# Motor_Driver.net
KiCad netlist of a schematic drawn in Altium Designer
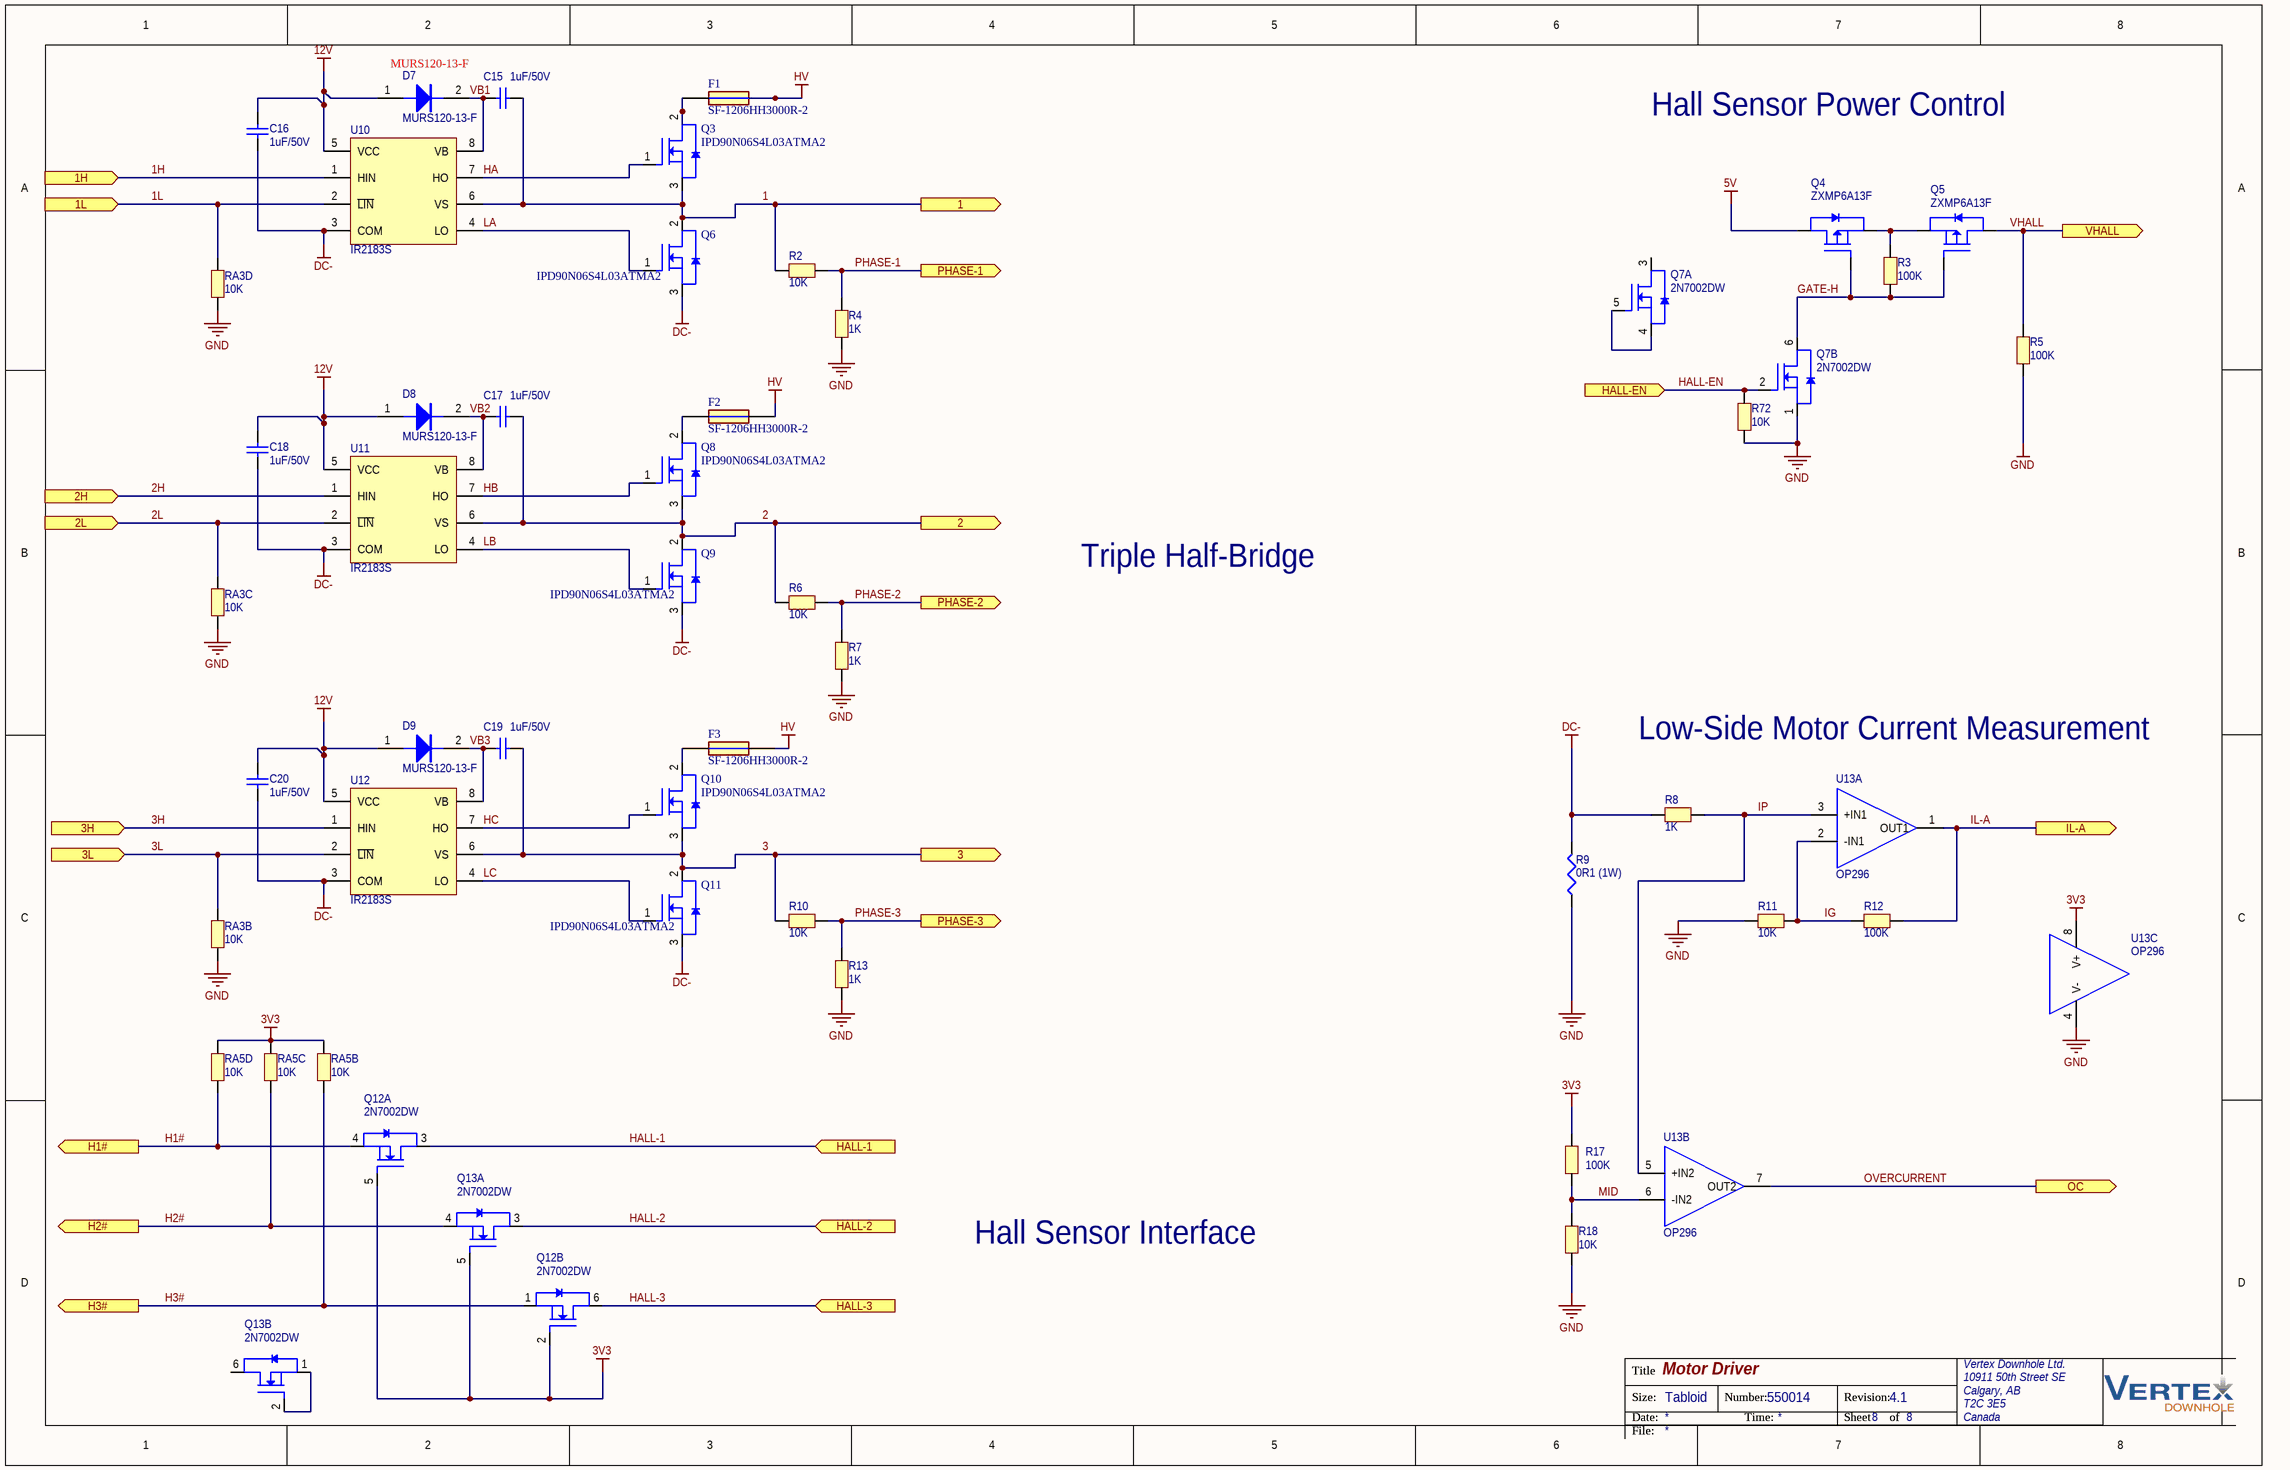
[diagram p0: Motor Driver.SchDoc]

(export (version "E")
  (design (tool "Eeschema 10.0.6"))
  (components
    (comp (ref "C15")
      (value "1uF/50V")
      (footprint "1206-CR")
      (description "Capacitor")
      (fields (field (name "MANUFACTURER") "Murata Electronics North America"))
      (libsource (lib "Miscellaneous Devices") (part "Cap"))
    )
    (comp (ref "C16")
      (value "1uF/50V")
      (footprint "1206-CR")
      (description "Capacitor")
      (fields (field (name "MANUFACTURER") "Murata Electronics North America"))
      (libsource (lib "Miscellaneous Devices") (part "Cap"))
    )
    (comp (ref "C17")
      (value "1uF/50V")
      (footprint "1206-CR")
      (description "Capacitor")
      (fields (field (name "MANUFACTURER") "Murata Electronics North America"))
      (libsource (lib "Miscellaneous Devices") (part "Cap"))
    )
    (comp (ref "C18")
      (value "1uF/50V")
      (footprint "1206-CR")
      (description "Capacitor")
      (fields (field (name "MANUFACTURER") "Murata Electronics North America"))
      (libsource (lib "Miscellaneous Devices") (part "Cap"))
    )
    (comp (ref "C19")
      (value "1uF/50V")
      (footprint "1206-CR")
      (description "Capacitor")
      (fields (field (name "MANUFACTURER") "Murata Electronics North America"))
      (libsource (lib "Miscellaneous Devices") (part "Cap"))
    )
    (comp (ref "C20")
      (value "1uF/50V")
      (footprint "1206-CR")
      (description "Capacitor")
      (fields (field (name "MANUFACTURER") "Murata Electronics North America"))
      (libsource (lib "Miscellaneous Devices") (part "Cap"))
    )
    (comp (ref "D7")
      (value "MURS120-13-F")
      (footprint "SMB-D")
      (description "Diode")
      (fields (field (name "MANUFACTURER") "Diodes Inc."))
      (libsource (lib "Pulser Driver 4,2") (part "DIODE_1"))
    )
    (comp (ref "D8")
      (value "MURS120-13-F")
      (footprint "SMB-D")
      (description "Diode")
      (fields (field (name "MANUFACTURER") "Diodes Inc."))
      (libsource (lib "Pulser Driver 4,2") (part "DIODE_1"))
    )
    (comp (ref "D9")
      (value "MURS120-13-F")
      (footprint "SMB-D")
      (description "Diode")
      (fields (field (name "MANUFACTURER") "Diodes Inc."))
      (libsource (lib "Pulser Driver 4,2") (part "DIODE_1"))
    )
    (comp (ref "F1")
      (value "SF-1206HH3000R-2")
      (footprint "SF1206HH3000R2")
      (description "1206 high-current met-foil. 30A")
      (fields (field (name "MOUSER PART NUMBER") "652-SF-1206HH3000R-2"))
      (libsource (lib "SF-1206HH3000R-2") (part "SF-1206HH3000R-2"))
    )
    (comp (ref "F2")
      (value "SF-1206HH3000R-2")
      (footprint "SF1206HH3000R2")
      (description "1206 high-current met-foil. 30A")
      (fields (field (name "MOUSER PART NUMBER") "652-SF-1206HH3000R-2"))
      (libsource (lib "SF-1206HH3000R-2") (part "SF-1206HH3000R-2"))
    )
    (comp (ref "F3")
      (value "SF-1206HH3000R-2")
      (footprint "SF1206HH3000R2")
      (description "1206 high-current met-foil. 30A")
      (fields (field (name "MOUSER PART NUMBER") "652-SF-1206HH3000R-2"))
      (libsource (lib "SF-1206HH3000R-2") (part "SF-1206HH3000R-2"))
    )
    (comp (ref "Q3")
      (value "IPD90N06S4L03ATMA2")
      (footprint "TO228P998X235-3N-2-V")
      (description "MOSFET N-CH 60V 90A TO252-31")
      (libsource (lib "FET") (part "IPD90N06S4L03ATMA2"))
    )
    (comp (ref "Q4")
      (value "ZXMP6A13F")
      (footprint "DGS")
      (description "ZXMP6A13F 60V P-channel FET")
      (fields (field (name "MANUFACTURER") "Diodes/Zetex"))
      (libsource (lib "FET") (part "Si2323DS"))
    )
    (comp (ref "Q5")
      (value "ZXMP6A13F")
      (footprint "SOT-23_DIO")
      (description "ZXMP6A13F 60V P-channel FET")
      (fields (field (name "MANUFACTURER") "Diodes/Zetex"))
      (libsource (lib "FET") (part "Si2323DS"))
    )
    (comp (ref "Q6")
      (value "IPD90N06S4L03ATMA2")
      (footprint "TO228P998X235-3N-2-V")
      (description "MOSFET N-CH 60V 90A TO252-31")
      (libsource (lib "FET") (part "IPD90N06S4L03ATMA2"))
    )
    (comp (ref "Q7")
      (value "2N7002DW")
      (footprint "DCK-6")
      (description "2N7002DW Dual N-Channel FET SC-70-6")
      (fields (field (name "MANUFACTURER") "Fairchild Semiconductor"))
      (libsource (lib "FET") (part "2N7002DW"))
    )
    (comp (ref "Q8")
      (value "IPD90N06S4L03ATMA2")
      (footprint "TO228P998X235-3N-2-V")
      (description "MOSFET N-CH 60V 90A TO252-31")
      (libsource (lib "FET") (part "IPD90N06S4L03ATMA2"))
    )
    (comp (ref "Q9")
      (value "IPD90N06S4L03ATMA2")
      (footprint "TO228P998X235-3N-2-V")
      (description "MOSFET N-CH 60V 90A TO252-31")
      (libsource (lib "FET") (part "IPD90N06S4L03ATMA2"))
    )
    (comp (ref "Q10")
      (value "IPD90N06S4L03ATMA2")
      (footprint "TO228P998X235-3N-2-V")
      (description "MOSFET N-CH 60V 90A TO252-31")
      (libsource (lib "FET") (part "IPD90N06S4L03ATMA2"))
    )
    (comp (ref "Q11")
      (value "IPD90N06S4L03ATMA2")
      (footprint "TO228P998X235-3N-2-V")
      (description "MOSFET N-CH 60V 90A TO252-31")
      (libsource (lib "FET") (part "IPD90N06S4L03ATMA2"))
    )
    (comp (ref "Q12")
      (value "2N7002DW")
      (footprint "DCK-6")
      (description "2N7002DW Dual N-Channel FET SC-70-6")
      (fields (field (name "MANUFACTURER") "Fairchild Semiconductor"))
      (libsource (lib "FET") (part "2N7002DW"))
    )
    (comp (ref "Q13")
      (value "2N7002DW")
      (footprint "DCK-6")
      (description "2N7002DW Dual N-Channel FET SC-70-6")
      (fields (field (name "MANUFACTURER") "Fairchild Semiconductor"))
      (libsource (lib "FET") (part "2N7002DW"))
    )
    (comp (ref "R2")
      (value "10K")
      (footprint "0805-CR")
      (description "Resistor")
      (fields (field (name "MANUFACTURER") "Yageo"))
      (libsource (lib "Resistors") (part "RES"))
    )
    (comp (ref "R3")
      (value "100K")
      (footprint "0805-CR")
      (description "Resistor")
      (fields (field (name "MANUFACTURER") "Yageo"))
      (libsource (lib "") (part "RES_5"))
    )
    (comp (ref "R4")
      (value "1K")
      (footprint "0805-CR")
      (description "Resistor")
      (fields (field (name "MANUFACTURER") "Yageo"))
      (libsource (lib "") (part "RES_3"))
    )
    (comp (ref "R5")
      (value "100K")
      (footprint "0805-CR")
      (description "Resistor")
      (fields (field (name "MANUFACTURER") "Yageo"))
      (libsource (lib "") (part "RES_1"))
    )
    (comp (ref "R6")
      (value "10K")
      (footprint "0805-CR")
      (description "Resistor")
      (fields (field (name "MANUFACTURER") "Yageo"))
      (libsource (lib "Resistors") (part "RES"))
    )
    (comp (ref "R7")
      (value "1K")
      (footprint "0805-CR")
      (description "Resistor")
      (fields (field (name "MANUFACTURER") "Yageo"))
      (libsource (lib "") (part "RES_3"))
    )
    (comp (ref "R8")
      (value "1K")
      (footprint "0805-CR")
      (description "Resistor")
      (fields (field (name "MANUFACTURER") "Yageo"))
      (libsource (lib "Resistors") (part "RES"))
    )
    (comp (ref "R9")
      (value "0R1 (1W)")
      (footprint "2512-CR")
      (description "RES 0.1 OHM 1% 1W 2512")
      (fields (field (name "MANUFACTURER") "Vishay/Dale"))
      (libsource (lib "*") (part "RES1"))
    )
    (comp (ref "R10")
      (value "10K")
      (footprint "0805-CR")
      (description "Resistor")
      (fields (field (name "MANUFACTURER") "Yageo"))
      (libsource (lib "Resistors") (part "RES"))
    )
    (comp (ref "R11")
      (value "10K")
      (footprint "0805-CR")
      (description "Resistor")
      (fields (field (name "MANUFACTURER") "Yageo"))
      (libsource (lib "Resistors") (part "RES"))
    )
    (comp (ref "R12")
      (value "100K")
      (footprint "0805-CR")
      (description "Resistor")
      (fields (field (name "MANUFACTURER") "Yageo"))
      (libsource (lib "") (part "RES_3"))
    )
    (comp (ref "R13")
      (value "1K")
      (footprint "0805-CR")
      (description "Resistor")
      (fields (field (name "MANUFACTURER") "Yageo"))
      (libsource (lib "") (part "RES_3"))
    )
    (comp (ref "R17")
      (value "100K")
      (footprint "0805-CR")
      (description "Resistor")
      (fields (field (name "MANUFACTURER") "Yageo"))
      (libsource (lib "") (part "RES_4"))
    )
    (comp (ref "R18")
      (value "10K")
      (footprint "0805-CR")
      (description "Resistor")
      (fields (field (name "MANUFACTURER") "Yageo"))
      (libsource (lib "") (part "RES_1"))
    )
    (comp (ref "R72")
      (value "10K")
      (footprint "0805-CR")
      (description "Resistor")
      (fields (field (name "MANUFACTURER") "Yageo"))
      (libsource (lib "") (part "RES_2"))
    )
    (comp (ref "RA3")
      (value "10K")
      (footprint "742x083")
      (description "742 4-Isolated 50V (0603x4) Resistor Array")
      (fields (field (name "MANUFACTURER") "CTS Resistor Products"))
      (libsource (lib "Resistor Networks") (part "742x083"))
    )
    (comp (ref "RA5")
      (value "10K")
      (footprint "742x083")
      (description "742 4-Isolated 50V (0603x4) Resistor Array")
      (fields (field (name "MANUFACTURER") "CTS Resistor Products"))
      (libsource (lib "Resistor Networks") (part "742x083"))
    )
    (comp (ref "U10")
      (value "IR2183S")
      (footprint "Pulser Driver:D8")
      (description "IR2183S Dual High/Low Side FET Driver")
      (fields (field (name "MANUFACTURER") "International Rectifier"))
      (libsource (lib "New IR FET Drivers") (part "IR2183S"))
    )
    (comp (ref "U11")
      (value "IR2183S")
      (footprint "Pulser Driver:D8")
      (description "IR2183S Dual High/Low Side FET Driver")
      (fields (field (name "MANUFACTURER") "International Rectifier"))
      (libsource (lib "New IR FET Drivers") (part "IR2183S"))
    )
    (comp (ref "U12")
      (value "IR2183S")
      (footprint "Pulser Driver:D8")
      (description "IR2183S Dual High/Low Side FET Driver")
      (fields (field (name "MANUFACTURER") "International Rectifier"))
      (libsource (lib "New IR FET Drivers") (part "IR2183S"))
    )
    (comp (ref "U13")
      (value "OP296")
      (footprint "D8")
      (description "OP296 Micropower Op Amp")
      (fields (field (name "MANUFACTURER") "Analog Devices Inc"))
      (libsource (lib "ADI") (part "OP296"))
    )
  )
  (nets
    (net (code "1") (name "/1") (class "Default")
      (node (ref "C15") (pin "1") (pinfunction "1_1") (pintype "passive"))
      (node (ref "Q3") (pin "3") (pinfunction "S_3") (pintype "passive"))
      (node (ref "Q6") (pin "2") (pinfunction "D_2") (pintype "passive"))
      (node (ref "R2") (pin "1") (pinfunction "1_1") (pintype "passive"))
      (node (ref "U10") (pin "6") (pinfunction "VS_6") (pintype "passive"))
    )
    (net (code "2") (name "/1H") (class "Default")
      (node (ref "U10") (pin "1") (pinfunction "HIN_1") (pintype "passive"))
    )
    (net (code "3") (name "/1L") (class "Default")
      (node (ref "RA3") (pin "7") (pinfunction "7_7") (pintype "passive"))
      (node (ref "U10") (pin "2") (pinfunction "~{LIN}_2") (pintype "passive"))
    )
    (net (code "4") (name "/2") (class "Default")
      (node (ref "C17") (pin "1") (pinfunction "1_1") (pintype "passive"))
      (node (ref "Q8") (pin "3") (pinfunction "S_3") (pintype "passive"))
      (node (ref "Q9") (pin "2") (pinfunction "D_2") (pintype "passive"))
      (node (ref "R6") (pin "1") (pinfunction "1_1") (pintype "passive"))
      (node (ref "U11") (pin "6") (pinfunction "VS_6") (pintype "passive"))
    )
    (net (code "5") (name "/2H") (class "Default")
      (node (ref "U11") (pin "1") (pinfunction "HIN_1") (pintype "passive"))
    )
    (net (code "6") (name "/2L") (class "Default")
      (node (ref "RA3") (pin "5") (pinfunction "5_5") (pintype "passive"))
      (node (ref "U11") (pin "2") (pinfunction "~{LIN}_2") (pintype "passive"))
    )
    (net (code "7") (name "/3") (class "Default")
      (node (ref "C19") (pin "1") (pinfunction "1_1") (pintype "passive"))
      (node (ref "Q10") (pin "3") (pinfunction "S_3") (pintype "passive"))
      (node (ref "Q11") (pin "2") (pinfunction "D_2") (pintype "passive"))
      (node (ref "R10") (pin "1") (pinfunction "1_1") (pintype "passive"))
      (node (ref "U12") (pin "6") (pinfunction "VS_6") (pintype "passive"))
    )
    (net (code "8") (name "/3H") (class "Default")
      (node (ref "U12") (pin "1") (pinfunction "HIN_1") (pintype "passive"))
    )
    (net (code "9") (name "/3L") (class "Default")
      (node (ref "RA3") (pin "3") (pinfunction "3_3") (pintype "passive"))
      (node (ref "U12") (pin "2") (pinfunction "~{LIN}_2") (pintype "passive"))
    )
    (net (code "10") (name "/GATE-H") (class "Default")
      (node (ref "Q4") (pin "1") (pinfunction "G_1") (pintype "passive"))
      (node (ref "Q5") (pin "1") (pinfunction "G_1") (pintype "passive"))
      (node (ref "Q7") (pin "6") (pinfunction "D2_6") (pintype "passive"))
      (node (ref "R3") (pin "1") (pinfunction "1_1") (pintype "passive"))
    )
    (net (code "11") (name "/H1#") (class "Default")
      (node (ref "Q12") (pin "4") (pinfunction "S1_4") (pintype "passive"))
      (node (ref "RA5") (pin "8") (pinfunction "8_8") (pintype "passive"))
    )
    (net (code "12") (name "/H2#") (class "Default")
      (node (ref "Q13") (pin "4") (pinfunction "S1_4") (pintype "passive"))
      (node (ref "RA5") (pin "6") (pinfunction "6_6") (pintype "passive"))
    )
    (net (code "13") (name "/H3#") (class "Default")
      (node (ref "Q12") (pin "1") (pinfunction "S2_1") (pintype "passive"))
      (node (ref "RA5") (pin "4") (pinfunction "4_4") (pintype "passive"))
    )
    (net (code "14") (name "/HA") (class "Default")
      (node (ref "Q3") (pin "1") (pinfunction "G_1") (pintype "passive"))
      (node (ref "U10") (pin "7") (pinfunction "HO_7") (pintype "passive"))
    )
    (net (code "15") (name "/HALL-1") (class "Default")
      (node (ref "Q12") (pin "3") (pinfunction "D1_3") (pintype "passive"))
    )
    (net (code "16") (name "/HALL-2") (class "Default")
      (node (ref "Q13") (pin "3") (pinfunction "D1_3") (pintype "passive"))
    )
    (net (code "17") (name "/HALL-3") (class "Default")
      (node (ref "Q12") (pin "6") (pinfunction "D2_6") (pintype "passive"))
    )
    (net (code "18") (name "/HALL-EN") (class "Default")
      (node (ref "Q7") (pin "2") (pinfunction "G2_2") (pintype "passive"))
      (node (ref "R72") (pin "1") (pinfunction "1_1") (pintype "passive"))
    )
    (net (code "19") (name "/HB") (class "Default")
      (node (ref "Q8") (pin "1") (pinfunction "G_1") (pintype "passive"))
      (node (ref "U11") (pin "7") (pinfunction "HO_7") (pintype "passive"))
    )
    (net (code "20") (name "/HC") (class "Default")
      (node (ref "Q10") (pin "1") (pinfunction "G_1") (pintype "passive"))
      (node (ref "U12") (pin "7") (pinfunction "HO_7") (pintype "passive"))
    )
    (net (code "21") (name "/IG") (class "Default")
      (node (ref "R11") (pin "2") (pinfunction "2_2") (pintype "passive"))
      (node (ref "R12") (pin "1") (pinfunction "1_1") (pintype "passive"))
      (node (ref "U13") (pin "2") (pinfunction "-IN1_2") (pintype "passive"))
    )
    (net (code "22") (name "/IL-A") (class "Default")
      (node (ref "R12") (pin "2") (pinfunction "2_2") (pintype "passive"))
      (node (ref "U13") (pin "1") (pinfunction "OUT1_1") (pintype "passive"))
    )
    (net (code "23") (name "/IP") (class "Default")
      (node (ref "R8") (pin "2") (pinfunction "2_2") (pintype "passive"))
      (node (ref "U13") (pin "3") (pinfunction "+IN1_3") (pintype "passive"))
      (node (ref "U13") (pin "5") (pinfunction "+IN2_5") (pintype "passive"))
    )
    (net (code "24") (name "/LA") (class "Default")
      (node (ref "Q6") (pin "1") (pinfunction "G_1") (pintype "passive"))
      (node (ref "U10") (pin "4") (pinfunction "LO_4") (pintype "passive"))
    )
    (net (code "25") (name "/LB") (class "Default")
      (node (ref "Q9") (pin "1") (pinfunction "G_1") (pintype "passive"))
      (node (ref "U11") (pin "4") (pinfunction "LO_4") (pintype "passive"))
    )
    (net (code "26") (name "/LC") (class "Default")
      (node (ref "Q11") (pin "1") (pinfunction "G_1") (pintype "passive"))
      (node (ref "U12") (pin "4") (pinfunction "LO_4") (pintype "passive"))
    )
    (net (code "27") (name "/MID") (class "Default")
      (node (ref "R17") (pin "1") (pinfunction "1_1") (pintype "passive"))
      (node (ref "R18") (pin "1") (pinfunction "1_1") (pintype "passive"))
      (node (ref "U13") (pin "6") (pinfunction "-IN2_6") (pintype "passive"))
    )
    (net (code "28") (name "/OVERCURRENT") (class "Default")
      (node (ref "U13") (pin "7") (pinfunction "OUT2_7") (pintype "passive"))
    )
    (net (code "29") (name "/PHASE-1") (class "Default")
      (node (ref "R2") (pin "2") (pinfunction "2_2") (pintype "passive"))
      (node (ref "R4") (pin "2") (pinfunction "2_2") (pintype "passive"))
    )
    (net (code "30") (name "/PHASE-2") (class "Default")
      (node (ref "R6") (pin "2") (pinfunction "2_2") (pintype "passive"))
      (node (ref "R7") (pin "2") (pinfunction "2_2") (pintype "passive"))
    )
    (net (code "31") (name "/PHASE-3") (class "Default")
      (node (ref "R10") (pin "2") (pinfunction "2_2") (pintype "passive"))
      (node (ref "R13") (pin "2") (pinfunction "2_2") (pintype "passive"))
    )
    (net (code "32") (name "/VB1") (class "Default")
      (node (ref "C15") (pin "2") (pinfunction "2_2") (pintype "passive"))
      (node (ref "D7") (pin "2") (pinfunction "K_2") (pintype "passive"))
      (node (ref "U10") (pin "8") (pinfunction "VB_8") (pintype "passive"))
    )
    (net (code "33") (name "/VB2") (class "Default")
      (node (ref "C17") (pin "2") (pinfunction "2_2") (pintype "passive"))
      (node (ref "D8") (pin "2") (pinfunction "K_2") (pintype "passive"))
      (node (ref "U11") (pin "8") (pinfunction "VB_8") (pintype "passive"))
    )
    (net (code "34") (name "/VB3") (class "Default")
      (node (ref "C19") (pin "2") (pinfunction "2_2") (pintype "passive"))
      (node (ref "D9") (pin "2") (pinfunction "K_2") (pintype "passive"))
      (node (ref "U12") (pin "8") (pinfunction "VB_8") (pintype "passive"))
    )
    (net (code "35") (name "/VHALL") (class "Default")
      (node (ref "Q5") (pin "3") (pinfunction "D_3") (pintype "passive"))
      (node (ref "R5") (pin "1") (pinfunction "1_1") (pintype "passive"))
    )
    (net (code "36") (name "3V3") (class "Default")
      (node (ref "Q12") (pin "2") (pinfunction "G2_2") (pintype "passive"))
      (node (ref "Q12") (pin "5") (pinfunction "G1_5") (pintype "passive"))
      (node (ref "Q13") (pin "5") (pinfunction "G1_5") (pintype "passive"))
      (node (ref "R17") (pin "2") (pinfunction "2_2") (pintype "passive"))
      (node (ref "RA5") (pin "3") (pinfunction "3_3") (pintype "passive"))
      (node (ref "RA5") (pin "5") (pinfunction "5_5") (pintype "passive"))
      (node (ref "RA5") (pin "7") (pinfunction "7_7") (pintype "passive"))
      (node (ref "U13") (pin "8") (pinfunction "V+_8") (pintype "passive"))
    )
    (net (code "37") (name "5V") (class "Default")
      (node (ref "Q4") (pin "3") (pinfunction "D_3") (pintype "passive"))
    )
    (net (code "38") (name "12V") (class "Default")
      (node (ref "C16") (pin "2") (pinfunction "2_2") (pintype "passive"))
      (node (ref "C18") (pin "2") (pinfunction "2_2") (pintype "passive"))
      (node (ref "C20") (pin "2") (pinfunction "2_2") (pintype "passive"))
      (node (ref "D7") (pin "1") (pinfunction "A_1") (pintype "passive"))
      (node (ref "D8") (pin "1") (pinfunction "A_1") (pintype "passive"))
      (node (ref "D9") (pin "1") (pinfunction "A_1") (pintype "passive"))
      (node (ref "U10") (pin "5") (pinfunction "VCC_5") (pintype "passive"))
      (node (ref "U11") (pin "5") (pinfunction "VCC_5") (pintype "passive"))
      (node (ref "U12") (pin "5") (pinfunction "VCC_5") (pintype "passive"))
    )
    (net (code "39") (name "DC-") (class "Default")
      (node (ref "C16") (pin "1") (pinfunction "1_1") (pintype "passive"))
      (node (ref "C18") (pin "1") (pinfunction "1_1") (pintype "passive"))
      (node (ref "C20") (pin "1") (pinfunction "1_1") (pintype "passive"))
      (node (ref "Q11") (pin "3") (pinfunction "S_3") (pintype "passive"))
      (node (ref "Q6") (pin "3") (pinfunction "S_3") (pintype "passive"))
      (node (ref "Q9") (pin "3") (pinfunction "S_3") (pintype "passive"))
      (node (ref "R8") (pin "1") (pinfunction "1_1") (pintype "passive"))
      (node (ref "R9") (pin "2") (pintype "passive"))
      (node (ref "U10") (pin "3") (pinfunction "COM_3") (pintype "passive"))
      (node (ref "U11") (pin "3") (pinfunction "COM_3") (pintype "passive"))
      (node (ref "U12") (pin "3") (pinfunction "COM_3") (pintype "passive"))
    )
    (net (code "40") (name "GND") (class "Default")
      (node (ref "Q7") (pin "1") (pinfunction "S2_1") (pintype "passive"))
      (node (ref "R11") (pin "1") (pinfunction "1_1") (pintype "passive"))
      (node (ref "R13") (pin "1") (pinfunction "1_1") (pintype "passive"))
      (node (ref "R18") (pin "2") (pinfunction "2_2") (pintype "passive"))
      (node (ref "R4") (pin "1") (pinfunction "1_1") (pintype "passive"))
      (node (ref "R5") (pin "2") (pinfunction "2_2") (pintype "passive"))
      (node (ref "R7") (pin "1") (pinfunction "1_1") (pintype "passive"))
      (node (ref "R72") (pin "2") (pinfunction "2_2") (pintype "passive"))
      (node (ref "R9") (pin "1") (pintype "passive"))
      (node (ref "RA3") (pin "4") (pinfunction "4_4") (pintype "passive"))
      (node (ref "RA3") (pin "6") (pinfunction "6_6") (pintype "passive"))
      (node (ref "RA3") (pin "8") (pinfunction "8_8") (pintype "passive"))
      (node (ref "U13") (pin "4") (pinfunction "V-_4") (pintype "passive"))
    )
    (net (code "41") (name "HV") (class "Default")
      (node (ref "F1") (pin "2") (pinfunction "2_2") (pintype "passive"))
      (node (ref "F2") (pin "2") (pinfunction "2_2") (pintype "passive"))
      (node (ref "F3") (pin "2") (pinfunction "2_2") (pintype "passive"))
    )
    (net (code "42") (name "Net-(Q3-D)") (class "Default")
      (node (ref "F1") (pin "1") (pinfunction "1_1") (pintype "passive"))
      (node (ref "Q3") (pin "2") (pinfunction "D_2") (pintype "passive"))
    )
    (net (code "43") (name "Net-(Q4-S)") (class "Default")
      (node (ref "Q4") (pin "2") (pinfunction "S_2") (pintype "passive"))
      (node (ref "Q5") (pin "2") (pinfunction "S_2") (pintype "passive"))
      (node (ref "R3") (pin "2") (pinfunction "2_2") (pintype "passive"))
    )
    (net (code "44") (name "Net-(Q7A-G1)") (class "Default")
      (node (ref "Q7") (pin "4") (pinfunction "S1_4") (pintype "passive"))
      (node (ref "Q7") (pin "5") (pinfunction "G1_5") (pintype "passive"))
    )
    (net (code "45") (name "Net-(Q8-D)") (class "Default")
      (node (ref "F2") (pin "1") (pinfunction "1_1") (pintype "passive"))
      (node (ref "Q8") (pin "2") (pinfunction "D_2") (pintype "passive"))
    )
    (net (code "46") (name "Net-(Q10-D)") (class "Default")
      (node (ref "F3") (pin "1") (pinfunction "1_1") (pintype "passive"))
      (node (ref "Q10") (pin "2") (pinfunction "D_2") (pintype "passive"))
    )
    (net (code "47") (name "Net-(Q13B-G2)") (class "Default")
      (node (ref "Q13") (pin "1") (pinfunction "S2_1") (pintype "passive"))
      (node (ref "Q13") (pin "2") (pinfunction "G2_2") (pintype "passive"))
    )
    (net (code "48") (name "unconnected-(Q7A-D1-Pad3)") (class "Default")
      (node (ref "Q7") (pin "3") (pinfunction "D1_3") (pintype "passive"))
    )
    (net (code "49") (name "unconnected-(Q13B-D2-Pad6)") (class "Default")
      (node (ref "Q13") (pin "6") (pinfunction "D2_6") (pintype "passive"))
    )
  )
)
